# RomeBoardV1.net
KiCad netlist of a schematic drawn in EAGLE
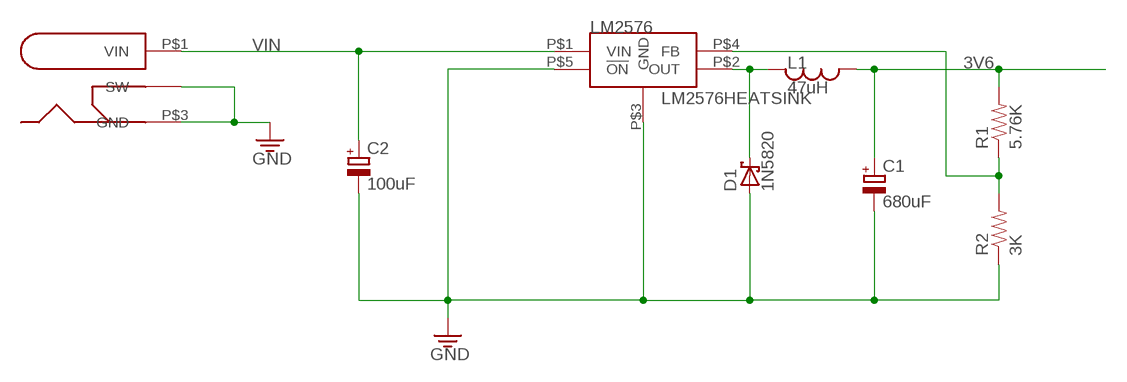
[diagram p0: schematic, sheet 1]
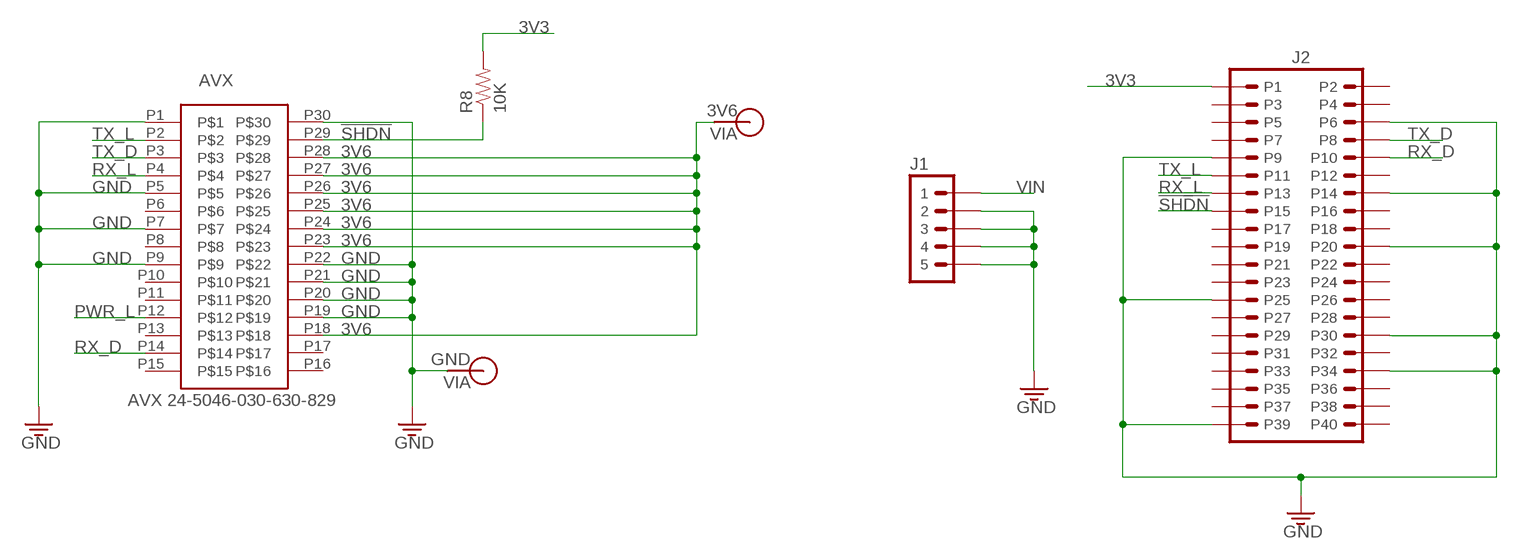
[diagram p1: schematic, sheet 2]
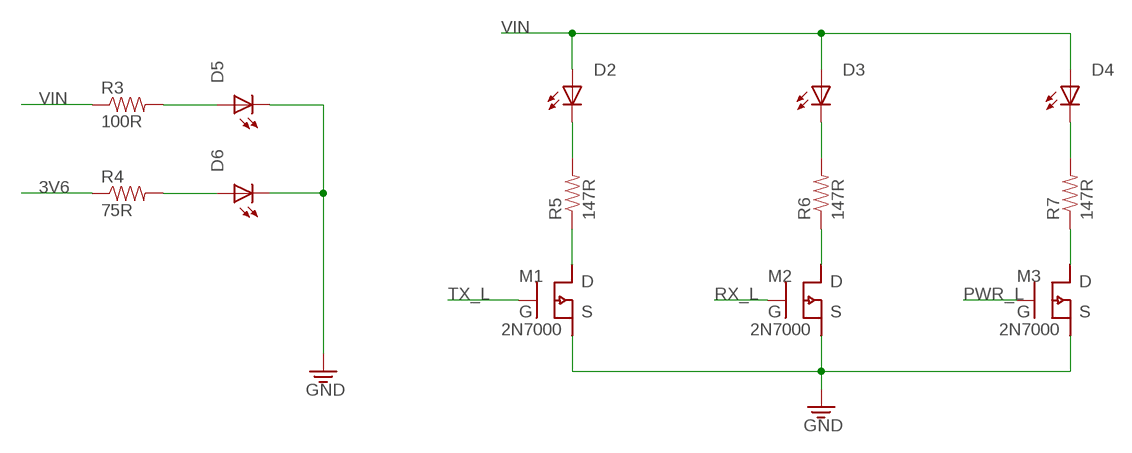
[diagram p2: schematic, sheet 3]

(export (version "E")
  (design (tool "Eeschema 10.0.6"))
  (components
    (comp (ref "AVX")
      (value "AVX-24-5046-030-630-829")
      (footprint "eagle-import:AVX-24-5046-630-829")
      (libsource (lib "eagle-import") (part "AVX-24-5046-030-630-829"))
    )
    (comp (ref "J1")
      (value "HEADER-5")
      (footprint "eagle-import:HEADER-05")
      (libsource (lib "eagle-import") (part "HEADER-5"))
    )
    (comp (ref "J2")
      (value "RASPBERRY-PI-HEADER")
      (footprint "eagle-import:HEADER-20X02")
      (libsource (lib "eagle-import") (part "RASPBERRY-PI-HEADER"))
    )
    (comp (ref "R8")
      (value "10K")
      (footprint "eagle-import:AXIAL-0.4")
      (libsource (lib "eagle-import") (part "RESISTOR-PTH0.4"))
    )
    (comp (ref "V4")
      (value "GND")
      (footprint "eagle-import:VIA-120MIL")
      (libsource (lib "eagle-import") (part "VIA-120MIL"))
    )
    (comp (ref "V5")
      (value "3V6")
      (footprint "eagle-import:VIA-120MIL")
      (libsource (lib "eagle-import") (part "VIA-120MIL"))
    )
    (comp (ref "C1")
      (value "680uF")
      (footprint "eagle-import:E5-10,5")
      (libsource (lib "eagle-import") (part "CPOL-EUE5-10.5"))
    )
    (comp (ref "C2")
      (value "100uF")
      (footprint "eagle-import:E5-10,5")
      (libsource (lib "eagle-import") (part "CPOL-EUE5-10.5"))
    )
    (comp (ref "D1")
      (value "1N5820")
      (footprint "eagle-import:DO-201AD")
      (libsource (lib "eagle-import") (part "1N5820"))
    )
    (comp (ref "L1")
      (value "47uH")
      (footprint "eagle-import:PE-53112NL")
      (libsource (lib "eagle-import") (part "INDPE-53112NL"))
    )
    (comp (ref "LM2576")
      (value "LM2576HEATSINK")
      (footprint "eagle-import:TO-220-5-HEATSINK")
      (libsource (lib "eagle-import") (part "LM2576HEATSINK"))
    )
    (comp (ref "R1")
      (value "5.76K")
      (footprint "eagle-import:AXIAL-0.4")
      (libsource (lib "eagle-import") (part "RESISTOR-PTH0.4"))
    )
    (comp (ref "R2")
      (value "3K")
      (footprint "eagle-import:AXIAL-0.4")
      (libsource (lib "eagle-import") (part "RESISTOR-PTH0.4"))
    )
    (comp (ref "U$2")
      (value "PJ-002A")
      (footprint "eagle-import:PJ-002A")
      (libsource (lib "eagle-import") (part "PJ-002A"))
    )
    (comp (ref "D2")
      (value "LEDTHRU-HOLE-CONNECTOR")
      (footprint "eagle-import:1X2-POL")
      (libsource (lib "eagle-import") (part "LEDTHRU-HOLE-CONNECTOR"))
    )
    (comp (ref "D3")
      (value "LEDTHRU-HOLE-CONNECTOR")
      (footprint "eagle-import:1X2-POL")
      (libsource (lib "eagle-import") (part "LEDTHRU-HOLE-CONNECTOR"))
    )
    (comp (ref "D4")
      (value "LEDTHRU-HOLE-CONNECTOR")
      (footprint "eagle-import:1X2-POL")
      (libsource (lib "eagle-import") (part "LEDTHRU-HOLE-CONNECTOR"))
    )
    (comp (ref "D5")
      (value "LEDTHRU-HOLE-CONNECTOR")
      (footprint "eagle-import:1X2-POL")
      (libsource (lib "eagle-import") (part "LEDTHRU-HOLE-CONNECTOR"))
    )
    (comp (ref "D6")
      (value "LEDTHRU-HOLE-CONNECTOR")
      (footprint "eagle-import:1X2-POL")
      (libsource (lib "eagle-import") (part "LEDTHRU-HOLE-CONNECTOR"))
    )
    (comp (ref "M1")
      (value "2N7000")
      (footprint "eagle-import:TO-923-MOS")
      (libsource (lib "eagle-import") (part "2N7000"))
    )
    (comp (ref "M2")
      (value "2N7000")
      (footprint "eagle-import:TO-923-MOS")
      (libsource (lib "eagle-import") (part "2N7000"))
    )
    (comp (ref "M3")
      (value "2N7000")
      (footprint "eagle-import:TO-923-MOS")
      (libsource (lib "eagle-import") (part "2N7000"))
    )
    (comp (ref "R3")
      (value "100R")
      (footprint "eagle-import:AXIAL-0.4")
      (libsource (lib "eagle-import") (part "RESISTOR-PTH0.4"))
    )
    (comp (ref "R4")
      (value "75R")
      (footprint "eagle-import:AXIAL-0.4")
      (libsource (lib "eagle-import") (part "RESISTOR-PTH0.4"))
    )
    (comp (ref "R5")
      (value "147R")
      (footprint "eagle-import:AXIAL-0.4")
      (libsource (lib "eagle-import") (part "RESISTOR-PTH0.4"))
    )
    (comp (ref "R6")
      (value "147R")
      (footprint "eagle-import:AXIAL-0.4")
      (libsource (lib "eagle-import") (part "RESISTOR-PTH0.4"))
    )
    (comp (ref "R7")
      (value "147R")
      (footprint "eagle-import:AXIAL-0.4")
      (libsource (lib "eagle-import") (part "RESISTOR-PTH0.4"))
    )
  )
  (nets
    (net (code "1") (name "3V3") (class "Default")
      (node (ref "J2") (pin "P1") (pinfunction "P1_P1") (pintype "passive"))
      (node (ref "R8") (pin "2") (pinfunction "2_2") (pintype "passive"))
    )
    (net (code "2") (name "3V6") (class "Default")
      (node (ref "AVX") (pin "P18") (pinfunction "P$18_P18") (pintype "bidirectional"))
      (node (ref "AVX") (pin "P23") (pinfunction "P$23_P23") (pintype "bidirectional"))
      (node (ref "AVX") (pin "P24") (pinfunction "P$24_P24") (pintype "bidirectional"))
      (node (ref "AVX") (pin "P25") (pinfunction "P$25_P25") (pintype "bidirectional"))
      (node (ref "AVX") (pin "P26") (pinfunction "P$26_P26") (pintype "bidirectional"))
      (node (ref "AVX") (pin "P27") (pinfunction "P$27_P27") (pintype "bidirectional"))
      (node (ref "AVX") (pin "P28") (pinfunction "P$28_P28") (pintype "bidirectional"))
      (node (ref "C1") (pin "+") (pinfunction "+_+") (pintype "passive"))
      (node (ref "L1") (pin "P$2") (pinfunction "P$2_P$2") (pintype "passive"))
      (node (ref "R1") (pin "2") (pinfunction "2_2") (pintype "passive"))
      (node (ref "R4") (pin "1") (pinfunction "1_1") (pintype "passive"))
      (node (ref "V5") (pin "P$1") (pinfunction "P$1_P$1") (pintype "bidirectional"))
    )
    (net (code "3") (name "GND") (class "Default")
      (node (ref "AVX") (pin "P1") (pinfunction "P$1_P1") (pintype "bidirectional"))
      (node (ref "AVX") (pin "P19") (pinfunction "P$19_P19") (pintype "bidirectional"))
      (node (ref "AVX") (pin "P20") (pinfunction "P$20_P20") (pintype "bidirectional"))
      (node (ref "AVX") (pin "P21") (pinfunction "P$21_P21") (pintype "bidirectional"))
      (node (ref "AVX") (pin "P22") (pinfunction "P$22_P22") (pintype "bidirectional"))
      (node (ref "AVX") (pin "P30") (pinfunction "P$30_P30") (pintype "bidirectional"))
      (node (ref "AVX") (pin "P5") (pinfunction "P$5_P5") (pintype "bidirectional"))
      (node (ref "AVX") (pin "P7") (pinfunction "P$7_P7") (pintype "bidirectional"))
      (node (ref "AVX") (pin "P9") (pinfunction "P$9_P9") (pintype "bidirectional"))
      (node (ref "C1") (pin "-") (pinfunction "-_-") (pintype "passive"))
      (node (ref "C2") (pin "-") (pinfunction "-_-") (pintype "passive"))
      (node (ref "D1") (pin "P$1") (pinfunction "A_P$1") (pintype "passive"))
      (node (ref "D5") (pin "2") (pinfunction "C_2") (pintype "passive"))
      (node (ref "D6") (pin "2") (pinfunction "C_2") (pintype "passive"))
      (node (ref "J1") (pin "2") (pinfunction "2_2") (pintype "passive"))
      (node (ref "J1") (pin "3") (pinfunction "3_3") (pintype "passive"))
      (node (ref "J1") (pin "4") (pinfunction "4_4") (pintype "passive"))
      (node (ref "J1") (pin "5") (pinfunction "5_5") (pintype "passive"))
      (node (ref "J2") (pin "P14") (pinfunction "P14_P14") (pintype "passive"))
      (node (ref "J2") (pin "P20") (pinfunction "P20_P20") (pintype "passive"))
      (node (ref "J2") (pin "P25") (pinfunction "P25_P25") (pintype "passive"))
      (node (ref "J2") (pin "P30") (pinfunction "P30_P30") (pintype "passive"))
      (node (ref "J2") (pin "P34") (pinfunction "P34_P34") (pintype "passive"))
      (node (ref "J2") (pin "P39") (pinfunction "P39_P39") (pintype "passive"))
      (node (ref "J2") (pin "P6") (pinfunction "P6_P6") (pintype "passive"))
      (node (ref "J2") (pin "P9") (pinfunction "P9_P9") (pintype "passive"))
      (node (ref "LM2576") (pin "P$3") (pinfunction "GND_P$3") (pintype "bidirectional"))
      (node (ref "LM2576") (pin "P$5") (pinfunction "~{ON}_P$5") (pintype "bidirectional"))
      (node (ref "M1") (pin "3") (pinfunction "S_3") (pintype "bidirectional"))
      (node (ref "M2") (pin "3") (pinfunction "S_3") (pintype "bidirectional"))
      (node (ref "M3") (pin "3") (pinfunction "S_3") (pintype "bidirectional"))
      (node (ref "R2") (pin "1") (pinfunction "1_1") (pintype "passive"))
      (node (ref "U$2") (pin "P$2") (pinfunction "SW_P$2") (pintype "bidirectional"))
      (node (ref "U$2") (pin "P$3") (pinfunction "GND_P$3") (pintype "bidirectional"))
      (node (ref "V4") (pin "P$1") (pinfunction "P$1_P$1") (pintype "bidirectional"))
    )
    (net (code "4") (name "Net-(D1-C)") (class "Default")
      (node (ref "D1") (pin "P$2") (pinfunction "C_P$2") (pintype "passive"))
      (node (ref "L1") (pin "P$1") (pinfunction "P$1_P$1") (pintype "passive"))
      (node (ref "LM2576") (pin "P$2") (pinfunction "OUT_P$2") (pintype "bidirectional"))
    )
    (net (code "5") (name "Net-(D2-C)") (class "Default")
      (node (ref "D2") (pin "2") (pinfunction "C_2") (pintype "passive"))
      (node (ref "R5") (pin "2") (pinfunction "2_2") (pintype "passive"))
    )
    (net (code "6") (name "Net-(D3-C)") (class "Default")
      (node (ref "D3") (pin "2") (pinfunction "C_2") (pintype "passive"))
      (node (ref "R6") (pin "2") (pinfunction "2_2") (pintype "passive"))
    )
    (net (code "7") (name "Net-(D4-C)") (class "Default")
      (node (ref "D4") (pin "2") (pinfunction "C_2") (pintype "passive"))
      (node (ref "R7") (pin "2") (pinfunction "2_2") (pintype "passive"))
    )
    (net (code "8") (name "Net-(D5-A)") (class "Default")
      (node (ref "D5") (pin "1") (pinfunction "A_1") (pintype "passive"))
      (node (ref "R3") (pin "2") (pinfunction "2_2") (pintype "passive"))
    )
    (net (code "9") (name "Net-(D6-A)") (class "Default")
      (node (ref "D6") (pin "1") (pinfunction "A_1") (pintype "passive"))
      (node (ref "R4") (pin "2") (pinfunction "2_2") (pintype "passive"))
    )
    (net (code "10") (name "Net-(LM2576-FB)") (class "Default")
      (node (ref "LM2576") (pin "P$4") (pinfunction "FB_P$4") (pintype "bidirectional"))
      (node (ref "R1") (pin "1") (pinfunction "1_1") (pintype "passive"))
      (node (ref "R2") (pin "2") (pinfunction "2_2") (pintype "passive"))
    )
    (net (code "11") (name "Net-(M1-D)") (class "Default")
      (node (ref "M1") (pin "1") (pinfunction "D_1") (pintype "bidirectional"))
      (node (ref "R5") (pin "1") (pinfunction "1_1") (pintype "passive"))
    )
    (net (code "12") (name "Net-(M2-D)") (class "Default")
      (node (ref "M2") (pin "1") (pinfunction "D_1") (pintype "bidirectional"))
      (node (ref "R6") (pin "1") (pinfunction "1_1") (pintype "passive"))
    )
    (net (code "13") (name "Net-(M3-D)") (class "Default")
      (node (ref "M3") (pin "1") (pinfunction "D_1") (pintype "bidirectional"))
      (node (ref "R7") (pin "1") (pinfunction "1_1") (pintype "passive"))
    )
    (net (code "14") (name "PWR_L") (class "Default")
      (node (ref "AVX") (pin "P12") (pinfunction "P$12_P12") (pintype "bidirectional"))
      (node (ref "M3") (pin "2") (pinfunction "G_2") (pintype "bidirectional"))
    )
    (net (code "15") (name "RX_D") (class "Default")
      (node (ref "AVX") (pin "P14") (pinfunction "P$14_P14") (pintype "bidirectional"))
      (node (ref "J2") (pin "P10") (pinfunction "P10_P10") (pintype "passive"))
    )
    (net (code "16") (name "RX_L") (class "Default")
      (node (ref "AVX") (pin "P4") (pinfunction "P$4_P4") (pintype "bidirectional"))
      (node (ref "J2") (pin "P13") (pinfunction "P13_P13") (pintype "passive"))
      (node (ref "M2") (pin "2") (pinfunction "G_2") (pintype "bidirectional"))
    )
    (net (code "17") (name "TX_D") (class "Default")
      (node (ref "AVX") (pin "P3") (pinfunction "P$3_P3") (pintype "bidirectional"))
      (node (ref "J2") (pin "P8") (pinfunction "P8_P8") (pintype "passive"))
    )
    (net (code "18") (name "TX_L") (class "Default")
      (node (ref "AVX") (pin "P2") (pinfunction "P$2_P2") (pintype "bidirectional"))
      (node (ref "J2") (pin "P11") (pinfunction "P11_P11") (pintype "passive"))
      (node (ref "M1") (pin "2") (pinfunction "G_2") (pintype "bidirectional"))
    )
    (net (code "19") (name "VIN") (class "Default")
      (node (ref "C2") (pin "+") (pinfunction "+_+") (pintype "passive"))
      (node (ref "D2") (pin "1") (pinfunction "A_1") (pintype "passive"))
      (node (ref "D3") (pin "1") (pinfunction "A_1") (pintype "passive"))
      (node (ref "D4") (pin "1") (pinfunction "A_1") (pintype "passive"))
      (node (ref "J1") (pin "1") (pinfunction "1_1") (pintype "passive"))
      (node (ref "LM2576") (pin "P$1") (pinfunction "VIN_P$1") (pintype "bidirectional"))
      (node (ref "R3") (pin "1") (pinfunction "1_1") (pintype "passive"))
      (node (ref "U$2") (pin "P$1") (pinfunction "VIN_P$1") (pintype "bidirectional"))
    )
    (net (code "20") (name "unconnected-(AVX-P$6-PadP6)") (class "Default")
      (node (ref "AVX") (pin "P6") (pinfunction "P$6_P6") (pintype "bidirectional"))
    )
    (net (code "21") (name "unconnected-(AVX-P$8-PadP8)") (class "Default")
      (node (ref "AVX") (pin "P8") (pinfunction "P$8_P8") (pintype "bidirectional"))
    )
    (net (code "22") (name "unconnected-(AVX-P$10-PadP10)") (class "Default")
      (node (ref "AVX") (pin "P10") (pinfunction "P$10_P10") (pintype "bidirectional"))
    )
    (net (code "23") (name "unconnected-(AVX-P$11-PadP11)") (class "Default")
      (node (ref "AVX") (pin "P11") (pinfunction "P$11_P11") (pintype "bidirectional"))
    )
    (net (code "24") (name "unconnected-(AVX-P$13-PadP13)") (class "Default")
      (node (ref "AVX") (pin "P13") (pinfunction "P$13_P13") (pintype "bidirectional"))
    )
    (net (code "25") (name "unconnected-(AVX-P$15-PadP15)") (class "Default")
      (node (ref "AVX") (pin "P15") (pinfunction "P$15_P15") (pintype "bidirectional"))
    )
    (net (code "26") (name "unconnected-(AVX-P$16-PadP16)") (class "Default")
      (node (ref "AVX") (pin "P16") (pinfunction "P$16_P16") (pintype "bidirectional"))
    )
    (net (code "27") (name "unconnected-(AVX-P$17-PadP17)") (class "Default")
      (node (ref "AVX") (pin "P17") (pinfunction "P$17_P17") (pintype "bidirectional"))
    )
    (net (code "28") (name "unconnected-(J2-PadP2)") (class "Default")
      (node (ref "J2") (pin "P2") (pinfunction "P2_P2") (pintype "passive"))
    )
    (net (code "29") (name "unconnected-(J2-PadP3)") (class "Default")
      (node (ref "J2") (pin "P3") (pinfunction "P3_P3") (pintype "passive"))
    )
    (net (code "30") (name "unconnected-(J2-PadP4)") (class "Default")
      (node (ref "J2") (pin "P4") (pinfunction "P4_P4") (pintype "passive"))
    )
    (net (code "31") (name "unconnected-(J2-PadP5)") (class "Default")
      (node (ref "J2") (pin "P5") (pinfunction "P5_P5") (pintype "passive"))
    )
    (net (code "32") (name "unconnected-(J2-PadP7)") (class "Default")
      (node (ref "J2") (pin "P7") (pinfunction "P7_P7") (pintype "passive"))
    )
    (net (code "33") (name "unconnected-(J2-PadP12)") (class "Default")
      (node (ref "J2") (pin "P12") (pinfunction "P12_P12") (pintype "passive"))
    )
    (net (code "34") (name "unconnected-(J2-PadP16)") (class "Default")
      (node (ref "J2") (pin "P16") (pinfunction "P16_P16") (pintype "passive"))
    )
    (net (code "35") (name "unconnected-(J2-PadP17)") (class "Default")
      (node (ref "J2") (pin "P17") (pinfunction "P17_P17") (pintype "passive"))
    )
    (net (code "36") (name "unconnected-(J2-PadP18)") (class "Default")
      (node (ref "J2") (pin "P18") (pinfunction "P18_P18") (pintype "passive"))
    )
    (net (code "37") (name "unconnected-(J2-PadP19)") (class "Default")
      (node (ref "J2") (pin "P19") (pinfunction "P19_P19") (pintype "passive"))
    )
    (net (code "38") (name "unconnected-(J2-PadP21)") (class "Default")
      (node (ref "J2") (pin "P21") (pinfunction "P21_P21") (pintype "passive"))
    )
    (net (code "39") (name "unconnected-(J2-PadP22)") (class "Default")
      (node (ref "J2") (pin "P22") (pinfunction "P22_P22") (pintype "passive"))
    )
    (net (code "40") (name "unconnected-(J2-PadP23)") (class "Default")
      (node (ref "J2") (pin "P23") (pinfunction "P23_P23") (pintype "passive"))
    )
    (net (code "41") (name "unconnected-(J2-PadP24)") (class "Default")
      (node (ref "J2") (pin "P24") (pinfunction "P24_P24") (pintype "passive"))
    )
    (net (code "42") (name "unconnected-(J2-PadP26)") (class "Default")
      (node (ref "J2") (pin "P26") (pinfunction "P26_P26") (pintype "passive"))
    )
    (net (code "43") (name "unconnected-(J2-PadP27)") (class "Default")
      (node (ref "J2") (pin "P27") (pinfunction "P27_P27") (pintype "passive"))
    )
    (net (code "44") (name "unconnected-(J2-PadP28)") (class "Default")
      (node (ref "J2") (pin "P28") (pinfunction "P28_P28") (pintype "passive"))
    )
    (net (code "45") (name "unconnected-(J2-PadP29)") (class "Default")
      (node (ref "J2") (pin "P29") (pinfunction "P29_P29") (pintype "passive"))
    )
    (net (code "46") (name "unconnected-(J2-PadP31)") (class "Default")
      (node (ref "J2") (pin "P31") (pinfunction "P31_P31") (pintype "passive"))
    )
    (net (code "47") (name "unconnected-(J2-PadP32)") (class "Default")
      (node (ref "J2") (pin "P32") (pinfunction "P32_P32") (pintype "passive"))
    )
    (net (code "48") (name "unconnected-(J2-PadP33)") (class "Default")
      (node (ref "J2") (pin "P33") (pinfunction "P33_P33") (pintype "passive"))
    )
    (net (code "49") (name "unconnected-(J2-PadP35)") (class "Default")
      (node (ref "J2") (pin "P35") (pinfunction "P35_P35") (pintype "passive"))
    )
    (net (code "50") (name "unconnected-(J2-PadP36)") (class "Default")
      (node (ref "J2") (pin "P36") (pinfunction "P36_P36") (pintype "passive"))
    )
    (net (code "51") (name "unconnected-(J2-PadP37)") (class "Default")
      (node (ref "J2") (pin "P37") (pinfunction "P37_P37") (pintype "passive"))
    )
    (net (code "52") (name "unconnected-(J2-PadP38)") (class "Default")
      (node (ref "J2") (pin "P38") (pinfunction "P38_P38") (pintype "passive"))
    )
    (net (code "53") (name "unconnected-(J2-PadP40)") (class "Default")
      (node (ref "J2") (pin "P40") (pinfunction "P40_P40") (pintype "passive"))
    )
    (net (code "54") (name "~{SHDN}") (class "Default")
      (node (ref "AVX") (pin "P29") (pinfunction "P$29_P29") (pintype "bidirectional"))
      (node (ref "J2") (pin "P15") (pinfunction "P15_P15") (pintype "passive"))
      (node (ref "R8") (pin "1") (pinfunction "1_1") (pintype "passive"))
    )
  )
)
